# Adorkable_Base_V2.net
KiCad netlist of a schematic drawn in EasyEDA Pro
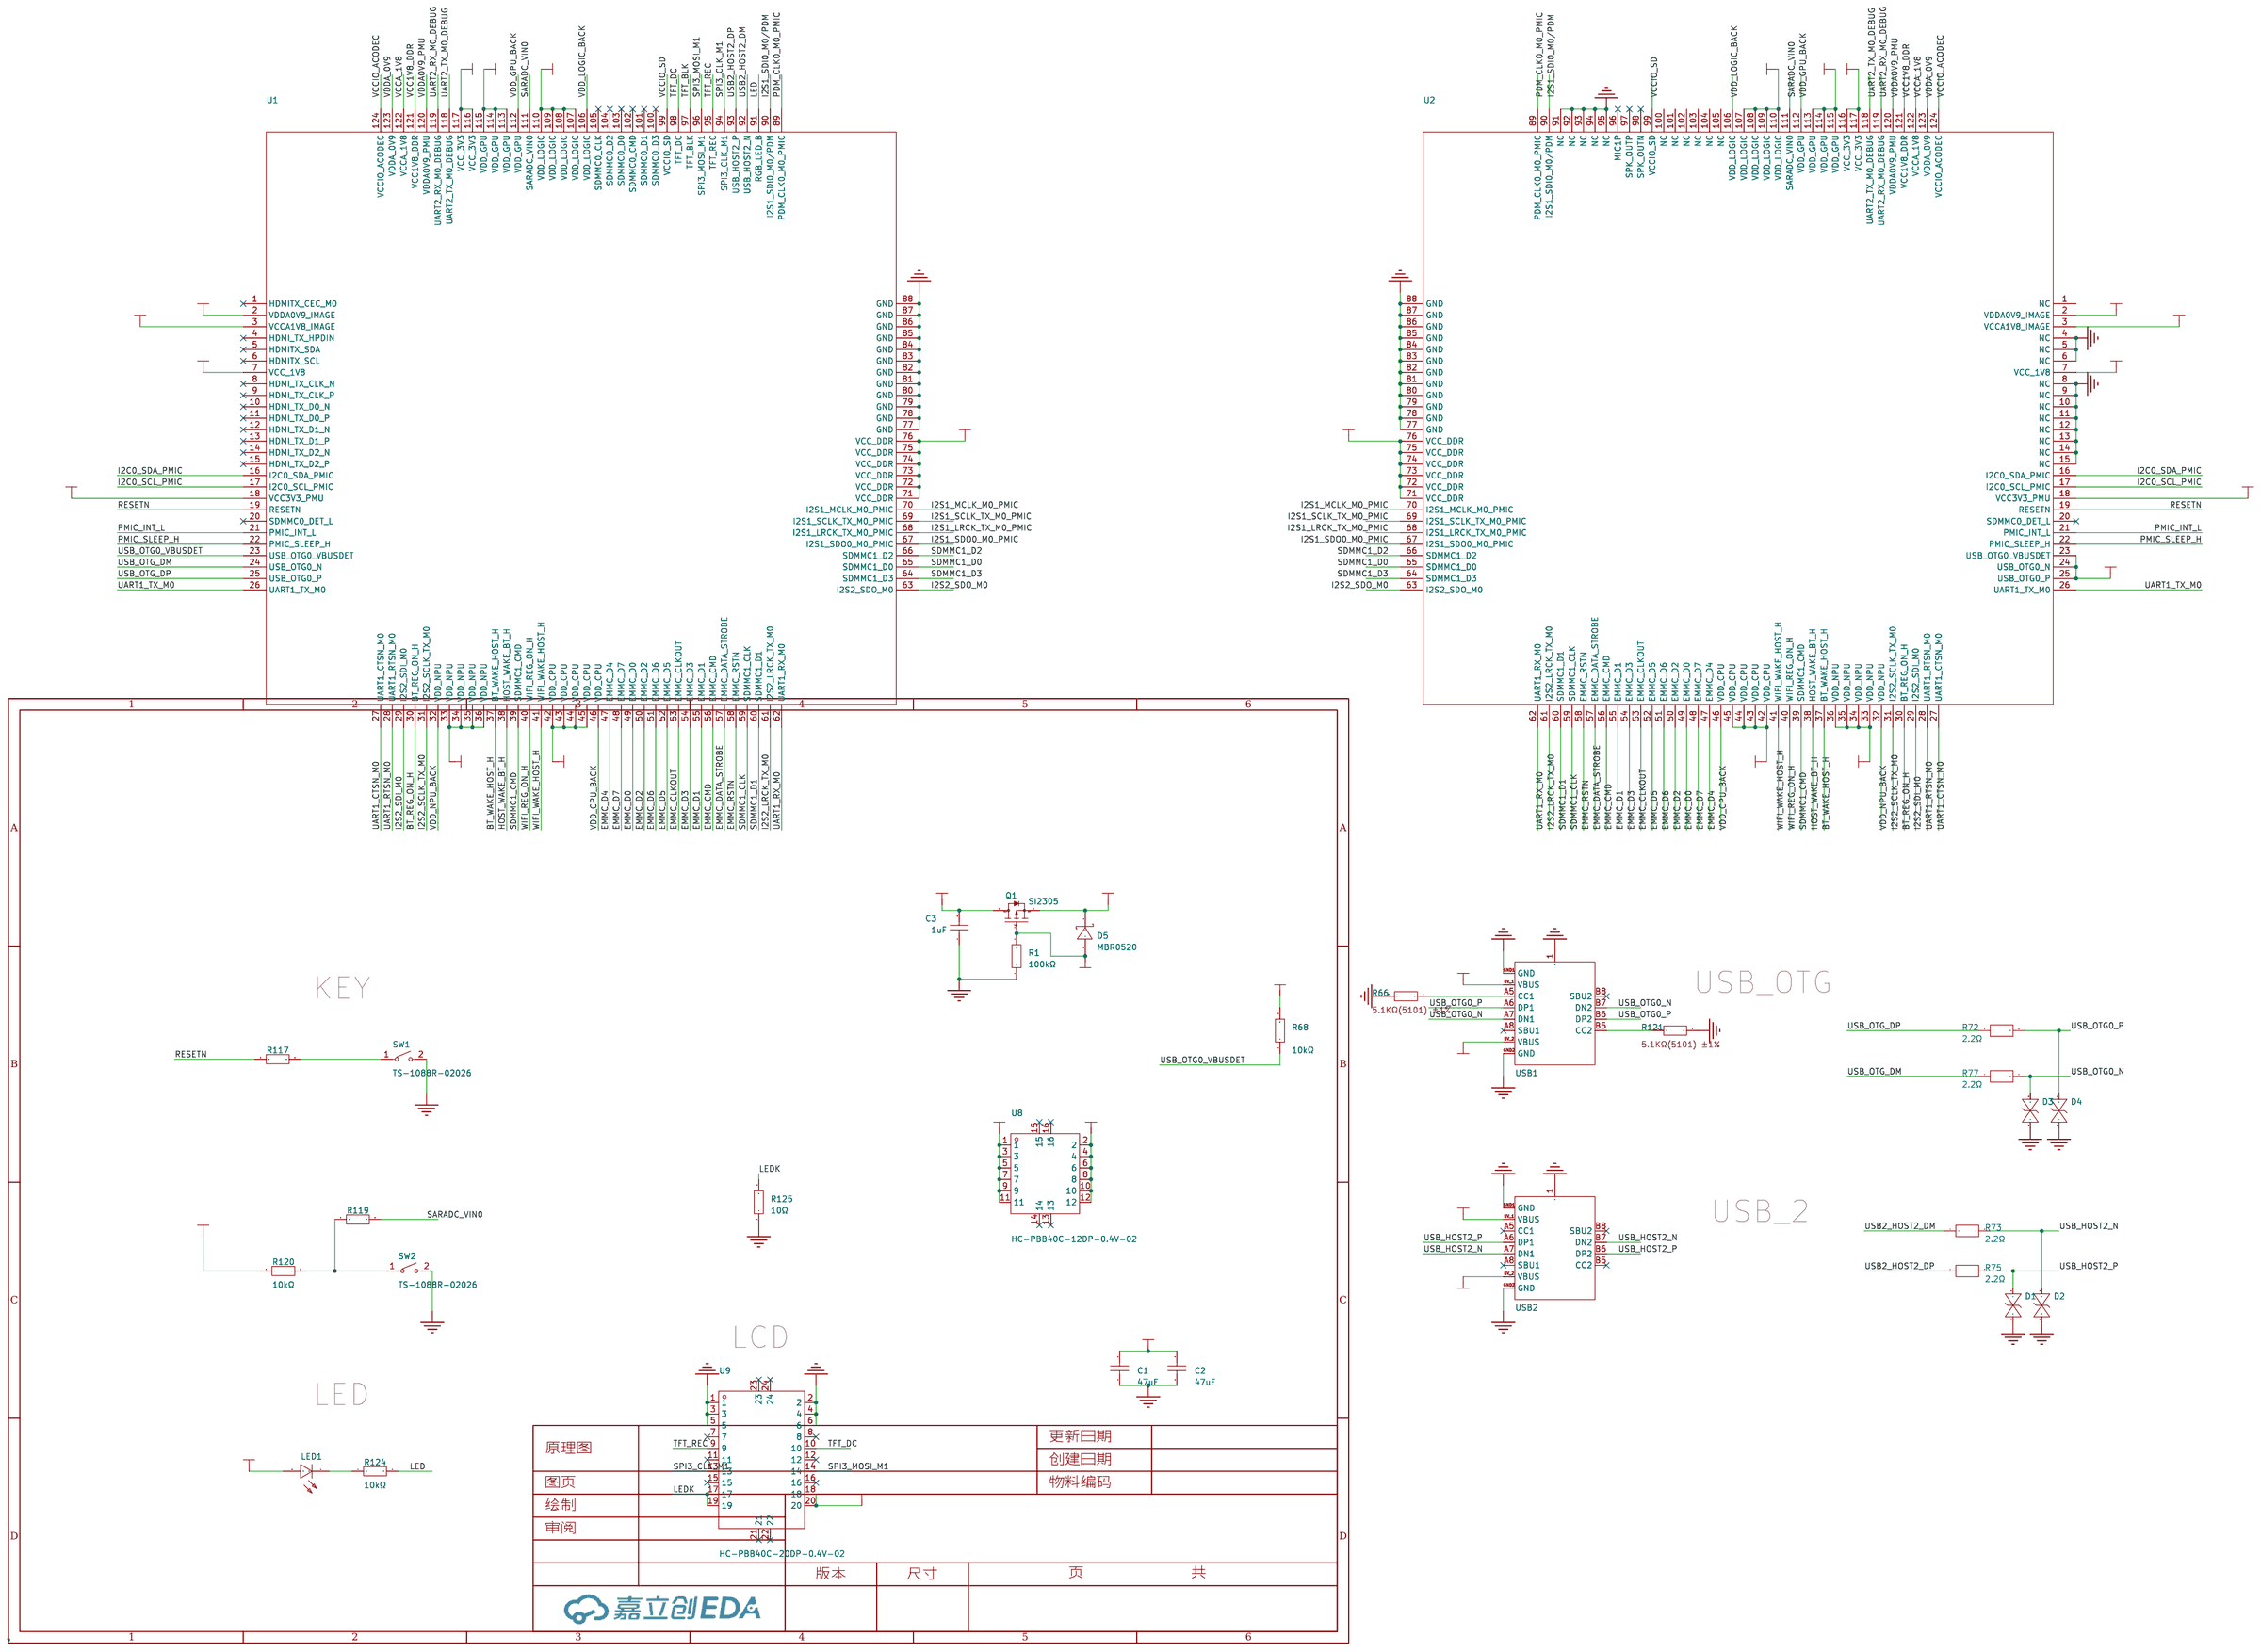
[diagram p0: schematic sheet]

(export (version "E")
  (design (tool "Eeschema 10.0.6"))
  (components
    (comp (ref "C1")
      (value "47uF")
      (footprint "easyedapro:C0603")
      (description "容值:47uF;精度:±20%;额定电压:6.3V;材质(温度系数):X5R;")
      (fields
        (field (name "Manufacturer Part") "GRM188R60J476ME15D")
        (field (name "Manufacturer") "muRata(村田)")
      )
      (libsource (lib "easyedapro") (part "GRM188R60J476ME15D"))
    )
    (comp (ref "C2")
      (value "47uF")
      (footprint "easyedapro:C0603")
      (description "容值:47uF;精度:±20%;额定电压:6.3V;材质(温度系数):X5R;")
      (fields
        (field (name "Manufacturer Part") "GRM188R60J476ME15D")
        (field (name "Manufacturer") "muRata(村田)")
      )
      (libsource (lib "easyedapro") (part "GRM188R60J476ME15D"))
    )
    (comp (ref "C3")
      (value "1uF")
      (footprint "easyedapro:C0402")
      (description "容值:1uF;精度:±10%;额定电压:10V;材质(温度系数):X5R;")
      (fields
        (field (name "Manufacturer Part") "CL05A105KP5NNNC")
        (field (name "Manufacturer") "SAMSUNG(三星)")
      )
      (libsource (lib "easyedapro") (part "CL05A105KP5NNNC"))
    )
    (comp (ref "D1")
      (value "KLXES15AAA1")
      (footprint "easyedapro:D0402-BI")
      (description "极性:双向;反向截止电压(Vrwm):5V;钳位电压(Vc)@Ipp:40V;")
      (fields (field (name "Manufacturer") "KUU"))
      (libsource (lib "easyedapro") (part "KLXES15AAA1"))
    )
    (comp (ref "D2")
      (value "KLXES15AAA1")
      (footprint "easyedapro:D0402-BI")
      (description "极性:双向;反向截止电压(Vrwm):5V;钳位电压(Vc)@Ipp:40V;")
      (fields (field (name "Manufacturer") "KUU"))
      (libsource (lib "easyedapro") (part "KLXES15AAA1"))
    )
    (comp (ref "D3")
      (value "KLXES15AAA1")
      (footprint "easyedapro:D0402-BI")
      (description "极性:双向;反向截止电压(Vrwm):5V;钳位电压(Vc)@Ipp:40V;")
      (fields (field (name "Manufacturer") "KUU"))
      (libsource (lib "easyedapro") (part "KLXES15AAA1"))
    )
    (comp (ref "D4")
      (value "KLXES15AAA1")
      (footprint "easyedapro:D0402-BI")
      (description "极性:双向;反向截止电压(Vrwm):5V;钳位电压(Vc)@Ipp:40V;")
      (fields (field (name "Manufacturer") "KUU"))
      (libsource (lib "easyedapro") (part "KLXES15AAA1"))
    )
    (comp (ref "D5")
      (value "MBR0520")
      (footprint "easyedapro:SOD-123_L2.8-W1.8-LS3.7-RD")
      (description "正向压降(Vf):450mV@500mA;直流反向耐压(Vr):20V;平均整流电流(Io):500mA;")
      (fields (field (name "Manufacturer") "CJ(江苏长电/长晶)"))
      (libsource (lib "easyedapro") (part "MBR0520"))
    )
    (comp (ref "LED1")
      (value "19-217/GHC-YR1S2/3T")
      (footprint "easyedapro:LED0603-RD")
      (description "发光颜色:翠绿;二极管配置:-;主波长:520nm~535nm;色温:-;功率:110mW;安装方式:-;")
      (fields (field (name "Manufacturer") "EVERLIGHT(亿光)"))
      (libsource (lib "easyedapro") (part "19-217/GHC-YR1S2/3T"))
    )
    (comp (ref "Q1")
      (value "SI2305")
      (footprint "easyedapro:SOT-23-3_L2.9-W1.3-P1.90-LS2.4-BR")
      (fields (field (name "Manufacturer") "Hottech(合科泰)"))
      (libsource (lib "easyedapro") (part "SI2305"))
    )
    (comp (ref "R1")
      (value "100kΩ")
      (footprint "easyedapro:R0402")
      (description "电阻类型:厚膜电阻;阻值:100kΩ;精度:±1%;功率:62.5mW;最大工作电压:50V;温度系数:±100ppm/°C;")
      (fields
        (field (name "Manufacturer Part") "0402WGF1003TCE")
        (field (name "Manufacturer") "UNI-ROYAL(厚声)")
      )
      (libsource (lib "easyedapro") (part "0402WGF1003TCE"))
    )
    (comp (ref "R66")
      (value "0402WGF5101TCE")
      (footprint "easyedapro:R0402")
      (fields (field (name "Manufacturer") "UNI-ROYAL(厚声)") (field (name "LCSC Part Name") "5.1KΩ(5101) ±1%"))
      (libsource (lib "easyedapro") (part "0402WGF5101TCE"))
    )
    (comp (ref "R68")
      (value "10kΩ")
      (footprint "easyedapro:R0402")
      (description "电阻类型:厚膜电阻;阻值:10kΩ;精度:±1%;功率:63mW;温度系数:±100ppm/K;最大工作电压:50V;工作温度范围:-55°C~+155°C;")
      (fields
        (field (name "Manufacturer Part") "CRCW040210K0FKED")
        (field (name "Manufacturer") "VISHAY(威世)")
      )
      (libsource (lib "easyedapro") (part "CRCW040210K0FKED"))
    )
    (comp (ref "R72")
      (value "2.2Ω")
      (footprint "easyedapro:R0402")
      (description "电阻类型:厚膜电阻;阻值:2.2Ω;精度:±5%;功率:100mW;温度系数:-100ppm/°C~+600ppm/°C;最大工作电压:-;工作温度范围:-55°C~+155°C;")
      (fields (field (name "Manufacturer Part") "ERJ2GEJ2R2X") (field (name "Manufacturer") "PANASONIC(松下)"))
      (libsource (lib "easyedapro") (part "ERJ2GEJ2R2X"))
    )
    (comp (ref "R73")
      (value "2.2Ω")
      (footprint "easyedapro:R0402")
      (description "电阻类型:厚膜电阻;阻值:2.2Ω;精度:±5%;功率:100mW;温度系数:-100ppm/°C~+600ppm/°C;最大工作电压:-;工作温度范围:-55°C~+155°C;")
      (fields (field (name "Manufacturer Part") "ERJ2GEJ2R2X") (field (name "Manufacturer") "PANASONIC(松下)"))
      (libsource (lib "easyedapro") (part "ERJ2GEJ2R2X"))
    )
    (comp (ref "R75")
      (value "2.2Ω")
      (footprint "easyedapro:R0402")
      (description "电阻类型:厚膜电阻;阻值:2.2Ω;精度:±5%;功率:100mW;温度系数:-100ppm/°C~+600ppm/°C;最大工作电压:-;工作温度范围:-55°C~+155°C;")
      (fields (field (name "Manufacturer Part") "ERJ2GEJ2R2X") (field (name "Manufacturer") "PANASONIC(松下)"))
      (libsource (lib "easyedapro") (part "ERJ2GEJ2R2X"))
    )
    (comp (ref "R77")
      (value "2.2Ω")
      (footprint "easyedapro:R0402")
      (description "电阻类型:厚膜电阻;阻值:2.2Ω;精度:±5%;功率:100mW;温度系数:-100ppm/°C~+600ppm/°C;最大工作电压:-;工作温度范围:-55°C~+155°C;")
      (fields (field (name "Manufacturer Part") "ERJ2GEJ2R2X") (field (name "Manufacturer") "PANASONIC(松下)"))
      (libsource (lib "easyedapro") (part "ERJ2GEJ2R2X"))
    )
    (comp (ref "R117")
      (value "0402WGF1000TCE")
      (footprint "easyedapro:R0402")
      (fields (field (name "Manufacturer") "UNI-ROYAL(厚声)"))
      (libsource (lib "easyedapro") (part "0402WGF1000TCE"))
    )
    (comp (ref "R119")
      (value "0402WGF1000TCE")
      (footprint "easyedapro:R0402")
      (fields (field (name "Manufacturer") "UNI-ROYAL(厚声)"))
      (libsource (lib "easyedapro") (part "0402WGF1000TCE"))
    )
    (comp (ref "R120")
      (value "10kΩ")
      (footprint "easyedapro:R0402")
      (description "电阻类型:厚膜电阻;阻值:10kΩ;精度:±1%;功率:62.5mW;")
      (fields
        (field (name "Manufacturer Part") "0402WGF1002TCE")
        (field (name "Manufacturer") "UNI-ROYAL(厚声)")
      )
      (libsource (lib "easyedapro") (part "0402WGF1002TCE"))
    )
    (comp (ref "R121")
      (value "0402WGF5101TCE")
      (footprint "easyedapro:R0402")
      (fields (field (name "Manufacturer") "UNI-ROYAL(厚声)") (field (name "LCSC Part Name") "5.1KΩ(5101) ±1%"))
      (libsource (lib "easyedapro") (part "0402WGF5101TCE"))
    )
    (comp (ref "R124")
      (value "10kΩ")
      (footprint "easyedapro:R0402")
      (description "电阻类型:厚膜电阻;阻值:10kΩ;精度:±1%;功率:62.5mW;")
      (fields
        (field (name "Manufacturer Part") "0402WGF1002TCE")
        (field (name "Manufacturer") "UNI-ROYAL(厚声)")
      )
      (libsource (lib "easyedapro") (part "0402WGF1002TCE"))
    )
    (comp (ref "R125")
      (value "10Ω")
      (footprint "easyedapro:R0402")
      (description "电阻类型:厚膜电阻;阻值:10Ω;精度:±1%;功率:62.5mW;最大工作电压:50V;温度系数:±200ppm/°C;")
      (fields
        (field (name "Manufacturer Part") "0402WGF100JTCE")
        (field (name "Manufacturer") "UNI-ROYAL(厚声)")
      )
      (libsource (lib "easyedapro") (part "0402WGF100JTCE"))
    )
    (comp (ref "SW1")
      (value "TS-1088R-02026")
      (footprint "easyedapro:SW-SMD_L3.9-W3.0-P4.45")
      (description "电路结构:单刀单掷;按钮形状:圆形按钮;安装方式:立贴;开关长度:3.9mm;开关宽度:2.93mm;开关高度:2mm;触点电流:50mA;额定电压(DC):12V;带灯:-;机械寿命:-;")
      (fields (field (name "Manufacturer") "XUNPU(讯普)"))
      (libsource (lib "easyedapro") (part "TS-1088R-02026"))
    )
    (comp (ref "SW2")
      (value "TS-1088R-02026")
      (footprint "easyedapro:SW-SMD_L3.9-W3.0-P4.45")
      (description "电路结构:单刀单掷;按钮形状:圆形按钮;安装方式:立贴;开关长度:3.9mm;开关宽度:2.93mm;开关高度:2mm;触点电流:50mA;额定电压(DC):12V;带灯:-;机械寿命:-;")
      (fields (field (name "Manufacturer") "XUNPU(讯普)"))
      (libsource (lib "easyedapro") (part "TS-1088R-02026"))
    )
    (comp (ref "U1") (value "~") (footprint "easyedapro:Core") (libsource (lib "easyedapro") (part "Core")))
    (comp (ref "U2") (value "~") (footprint "easyedapro:EXP") (libsource (lib "easyedapro") (part "EXP")))
    (comp (ref "U8")
      (value "HC-PBB40C-12DP-0.4V-02")
      (footprint "easyedapro:CONN-SMD_12P-P0.40_HCTL_HC-PBB40C-12DP-0.4V-02")
      (description "PIN总数:12P;间距:0.4mm;安装方式:立贴;排数:2;额定电流:300mA;工作温度:-35°C~+85°C;")
      (fields (field (name "Manufacturer") "HCTL(华灿天禄)"))
      (libsource (lib "easyedapro") (part "HC-PBB40C-12DP-0.4V-02"))
    )
    (comp (ref "U9")
      (value "HC-PBB40C-20DP-0.4V-02")
      (footprint "easyedapro:CONN-SMD_20P-P0.40_HCTL_HC-PBB40C-20DP-0.4V-02")
      (description "PIN总数:20P;间距:0.4mm;安装方式:立贴;排数:2;额定电流:300mA;工作温度:-35°C~+85°C;")
      (fields (field (name "Manufacturer") "HCTL(华灿天禄)"))
      (libsource (lib "easyedapro") (part "HC-PBB40C-20DP-0.4V-02"))
    )
    (comp (ref "USB1")
      (value "~")
      (footprint "easyedapro:TYPE-C-SMD_TYPE-CF3.1")
      (libsource (lib "easyedapro") (part "TYPE-C-16PIN"))
    )
    (comp (ref "USB2")
      (value "~")
      (footprint "easyedapro:TYPE-C-SMD_TYPE-CF3.1")
      (libsource (lib "easyedapro") (part "TYPE-C-16PIN"))
    )
  )
  (nets
    (net (code "1") (name "/BT_REG_ON_H") (class "Default")
      (node (ref "U1") (pin "30") (pinfunction "BT_REG_ON_H_30") (pintype "input"))
      (node (ref "U2") (pin "30") (pinfunction "BT_REG_ON_H_30") (pintype "input"))
    )
    (net (code "2") (name "/BT_WAKE_HOST_H") (class "Default")
      (node (ref "U1") (pin "37") (pinfunction "BT_WAKE_HOST_H_37") (pintype "input"))
      (node (ref "U2") (pin "37") (pinfunction "BT_WAKE_HOST_H_37") (pintype "input"))
    )
    (net (code "3") (name "/EMMC_CLKOUT") (class "Default")
      (node (ref "U1") (pin "53") (pinfunction "EMMC_CLKOUT_53") (pintype "input"))
      (node (ref "U2") (pin "53") (pinfunction "EMMC_CLKOUT_53") (pintype "input"))
    )
    (net (code "4") (name "/EMMC_CMD") (class "Default")
      (node (ref "U1") (pin "56") (pinfunction "EMMC_CMD_56") (pintype "input"))
      (node (ref "U2") (pin "56") (pinfunction "EMMC_CMD_56") (pintype "input"))
    )
    (net (code "5") (name "/EMMC_D0") (class "Default")
      (node (ref "U1") (pin "49") (pinfunction "EMMC_D0_49") (pintype "input"))
      (node (ref "U2") (pin "49") (pinfunction "EMMC_D0_49") (pintype "input"))
    )
    (net (code "6") (name "/EMMC_D1") (class "Default")
      (node (ref "U1") (pin "55") (pinfunction "EMMC_D1_55") (pintype "input"))
      (node (ref "U2") (pin "55") (pinfunction "EMMC_D1_55") (pintype "input"))
    )
    (net (code "7") (name "/EMMC_D2") (class "Default")
      (node (ref "U1") (pin "50") (pinfunction "EMMC_D2_50") (pintype "input"))
      (node (ref "U2") (pin "50") (pinfunction "EMMC_D2_50") (pintype "input"))
    )
    (net (code "8") (name "/EMMC_D3") (class "Default")
      (node (ref "U1") (pin "54") (pinfunction "EMMC_D3_54") (pintype "input"))
      (node (ref "U2") (pin "54") (pinfunction "EMMC_D3_54") (pintype "input"))
    )
    (net (code "9") (name "/EMMC_D4") (class "Default")
      (node (ref "U1") (pin "47") (pinfunction "EMMC_D4_47") (pintype "input"))
      (node (ref "U2") (pin "47") (pinfunction "EMMC_D4_47") (pintype "input"))
    )
    (net (code "10") (name "/EMMC_D5") (class "Default")
      (node (ref "U1") (pin "52") (pinfunction "EMMC_D5_52") (pintype "input"))
      (node (ref "U2") (pin "52") (pinfunction "EMMC_D5_52") (pintype "input"))
    )
    (net (code "11") (name "/EMMC_D6") (class "Default")
      (node (ref "U1") (pin "51") (pinfunction "EMMC_D6_51") (pintype "input"))
      (node (ref "U2") (pin "51") (pinfunction "EMMC_D6_51") (pintype "input"))
    )
    (net (code "12") (name "/EMMC_D7") (class "Default")
      (node (ref "U1") (pin "48") (pinfunction "EMMC_D7_48") (pintype "input"))
      (node (ref "U2") (pin "48") (pinfunction "EMMC_D7_48") (pintype "input"))
    )
    (net (code "13") (name "/EMMC_DATA_STROBE") (class "Default")
      (node (ref "U1") (pin "57") (pinfunction "EMMC_DATA_STROBE_57") (pintype "input"))
      (node (ref "U2") (pin "57") (pinfunction "EMMC_DATA_STROBE_57") (pintype "input"))
    )
    (net (code "14") (name "/EMMC_RSTN") (class "Default")
      (node (ref "U1") (pin "58") (pinfunction "EMMC_RSTN_58") (pintype "input"))
      (node (ref "U2") (pin "58") (pinfunction "EMMC_RSTN_58") (pintype "input"))
    )
    (net (code "15") (name "/HOST_WAKE_BT_H") (class "Default")
      (node (ref "U1") (pin "38") (pinfunction "HOST_WAKE_BT_H_38") (pintype "input"))
      (node (ref "U2") (pin "38") (pinfunction "HOST_WAKE_BT_H_38") (pintype "input"))
    )
    (net (code "16") (name "/I2C0_SCL_PMIC") (class "Default")
      (node (ref "U1") (pin "17") (pinfunction "I2C0_SCL_PMIC_17") (pintype "input"))
      (node (ref "U2") (pin "17") (pinfunction "I2C0_SCL_PMIC_17") (pintype "input"))
    )
    (net (code "17") (name "/I2C0_SDA_PMIC") (class "Default")
      (node (ref "U1") (pin "16") (pinfunction "I2C0_SDA_PMIC_16") (pintype "input"))
      (node (ref "U2") (pin "16") (pinfunction "I2C0_SDA_PMIC_16") (pintype "input"))
    )
    (net (code "18") (name "/I2S1_LRCK_TX_M0_PMIC") (class "Default")
      (node (ref "U1") (pin "68") (pinfunction "I2S1_LRCK_TX_M0_PMIC_68") (pintype "input"))
      (node (ref "U2") (pin "68") (pinfunction "I2S1_LRCK_TX_M0_PMIC_68") (pintype "input"))
    )
    (net (code "19") (name "/I2S1_MCLK_M0_PMIC") (class "Default")
      (node (ref "U1") (pin "70") (pinfunction "I2S1_MCLK_M0_PMIC_70") (pintype "input"))
      (node (ref "U2") (pin "70") (pinfunction "I2S1_MCLK_M0_PMIC_70") (pintype "input"))
    )
    (net (code "20") (name "/I2S1_SCLK_TX_M0_PMIC") (class "Default")
      (node (ref "U1") (pin "69") (pinfunction "I2S1_SCLK_TX_M0_PMIC_69") (pintype "input"))
      (node (ref "U2") (pin "69") (pinfunction "I2S1_SCLK_TX_M0_PMIC_69") (pintype "input"))
    )
    (net (code "21") (name "/I2S1_SDI0_M0{slash}PDM") (class "Default")
      (node (ref "U1") (pin "90") (pinfunction "I2S1_SDI0_M0/PDM_90") (pintype "input"))
      (node (ref "U2") (pin "90") (pinfunction "I2S1_SDI0_M0/PDM_90") (pintype "input"))
    )
    (net (code "22") (name "/I2S1_SDO0_M0_PMIC") (class "Default")
      (node (ref "U1") (pin "67") (pinfunction "I2S1_SDO0_M0_PMIC_67") (pintype "input"))
      (node (ref "U2") (pin "67") (pinfunction "I2S1_SDO0_M0_PMIC_67") (pintype "input"))
    )
    (net (code "23") (name "/I2S2_LRCK_TX_M0") (class "Default")
      (node (ref "U1") (pin "61") (pinfunction "I2S2_LRCK_TX_M0_61") (pintype "input"))
      (node (ref "U2") (pin "61") (pinfunction "I2S2_LRCK_TX_M0_61") (pintype "input"))
    )
    (net (code "24") (name "/I2S2_SCLK_TX_M0") (class "Default")
      (node (ref "U1") (pin "31") (pinfunction "I2S2_SCLK_TX_M0_31") (pintype "input"))
      (node (ref "U2") (pin "31") (pinfunction "I2S2_SCLK_TX_M0_31") (pintype "input"))
    )
    (net (code "25") (name "/I2S2_SDI_M0") (class "Default")
      (node (ref "U1") (pin "29") (pinfunction "I2S2_SDI_M0_29") (pintype "input"))
      (node (ref "U2") (pin "29") (pinfunction "I2S2_SDI_M0_29") (pintype "input"))
    )
    (net (code "26") (name "/I2S2_SDO_M0") (class "Default")
      (node (ref "U1") (pin "63") (pinfunction "I2S2_SDO_M0_63") (pintype "input"))
      (node (ref "U2") (pin "63") (pinfunction "I2S2_SDO_M0_63") (pintype "input"))
    )
    (net (code "27") (name "/LED") (class "Default")
      (node (ref "R124") (pin "2") (pinfunction "2_2") (pintype "input"))
      (node (ref "U1") (pin "91") (pinfunction "RGB_LED_B_91") (pintype "input"))
    )
    (net (code "28") (name "/LEDK") (class "Default")
      (node (ref "R125") (pin "2") (pinfunction "2_2") (pintype "input"))
      (node (ref "U9") (pin "17") (pinfunction "17_17") (pintype "unspecified"))
      (node (ref "U9") (pin "19") (pinfunction "19_19") (pintype "unspecified"))
    )
    (net (code "29") (name "/PDM_CLK0_M0_PMIC") (class "Default")
      (node (ref "U1") (pin "89") (pinfunction "PDM_CLK0_M0_PMIC_89") (pintype "input"))
      (node (ref "U2") (pin "89") (pinfunction "PDM_CLK0_M0_PMIC_89") (pintype "input"))
    )
    (net (code "30") (name "/PMIC_INT_L") (class "Default")
      (node (ref "U1") (pin "21") (pinfunction "PMIC_INT_L_21") (pintype "input"))
      (node (ref "U2") (pin "21") (pinfunction "PMIC_INT_L_21") (pintype "input"))
    )
    (net (code "31") (name "/PMIC_SLEEP_H") (class "Default")
      (node (ref "U1") (pin "22") (pinfunction "PMIC_SLEEP_H_22") (pintype "input"))
      (node (ref "U2") (pin "22") (pinfunction "PMIC_SLEEP_H_22") (pintype "input"))
    )
    (net (code "32") (name "/RESETN") (class "Default")
      (node (ref "R117") (pin "1") (pinfunction "1_1") (pintype "input"))
      (node (ref "U1") (pin "19") (pinfunction "RESETN_19") (pintype "input"))
      (node (ref "U2") (pin "19") (pinfunction "RESETN_19") (pintype "input"))
    )
    (net (code "33") (name "/SARADC_VIN0") (class "Default")
      (node (ref "R119") (pin "2") (pinfunction "2_2") (pintype "input"))
      (node (ref "U1") (pin "111") (pinfunction "SARADC_VIN0_111") (pintype "input"))
      (node (ref "U2") (pin "111") (pinfunction "SARADC_VIN0_111") (pintype "input"))
    )
    (net (code "34") (name "/SDMMC1_CLK") (class "Default")
      (node (ref "U1") (pin "59") (pinfunction "SDMMC1_CLK_59") (pintype "input"))
      (node (ref "U2") (pin "59") (pinfunction "SDMMC1_CLK_59") (pintype "input"))
    )
    (net (code "35") (name "/SDMMC1_CMD") (class "Default")
      (node (ref "U1") (pin "39") (pinfunction "SDMMC1_CMD_39") (pintype "input"))
      (node (ref "U2") (pin "39") (pinfunction "SDMMC1_CMD_39") (pintype "input"))
    )
    (net (code "36") (name "/SDMMC1_D0") (class "Default")
      (node (ref "U1") (pin "65") (pinfunction "SDMMC1_D0_65") (pintype "input"))
      (node (ref "U2") (pin "65") (pinfunction "SDMMC1_D0_65") (pintype "input"))
    )
    (net (code "37") (name "/SDMMC1_D1") (class "Default")
      (node (ref "U1") (pin "60") (pinfunction "SDMMC1_D1_60") (pintype "input"))
      (node (ref "U2") (pin "60") (pinfunction "SDMMC1_D1_60") (pintype "input"))
    )
    (net (code "38") (name "/SDMMC1_D2") (class "Default")
      (node (ref "U1") (pin "66") (pinfunction "SDMMC1_D2_66") (pintype "input"))
      (node (ref "U2") (pin "66") (pinfunction "SDMMC1_D2_66") (pintype "input"))
    )
    (net (code "39") (name "/SDMMC1_D3") (class "Default")
      (node (ref "U1") (pin "64") (pinfunction "SDMMC1_D3_64") (pintype "input"))
      (node (ref "U2") (pin "64") (pinfunction "SDMMC1_D3_64") (pintype "input"))
    )
    (net (code "40") (name "/SPI3_CLK_M1") (class "Default")
      (node (ref "U1") (pin "94") (pinfunction "SPI3_CLK_M1_94") (pintype "input"))
      (node (ref "U9") (pin "13") (pinfunction "13_13") (pintype "unspecified"))
    )
    (net (code "41") (name "/SPI3_MOSI_M1") (class "Default")
      (node (ref "U1") (pin "96") (pinfunction "SPI3_MOSI_M1_96") (pintype "input"))
      (node (ref "U9") (pin "14") (pinfunction "14_14") (pintype "unspecified"))
    )
    (net (code "42") (name "/TFT_BLK") (class "Default")
      (node (ref "U1") (pin "97") (pinfunction "TFT_BLK_97") (pintype "input"))
    )
    (net (code "43") (name "/TFT_DC") (class "Default")
      (node (ref "U1") (pin "98") (pinfunction "TFT_DC_98") (pintype "input"))
      (node (ref "U9") (pin "10") (pinfunction "10_10") (pintype "unspecified"))
    )
    (net (code "44") (name "/TFT_REC") (class "Default")
      (node (ref "U1") (pin "95") (pinfunction "TFT_REC_95") (pintype "input"))
      (node (ref "U9") (pin "9") (pinfunction "9_9") (pintype "unspecified"))
    )
    (net (code "45") (name "/UART1_CTSN_M0") (class "Default")
      (node (ref "U1") (pin "27") (pinfunction "UART1_CTSN_M0_27") (pintype "input"))
      (node (ref "U2") (pin "27") (pinfunction "UART1_CTSN_M0_27") (pintype "input"))
    )
    (net (code "46") (name "/UART1_RTSN_M0") (class "Default")
      (node (ref "U1") (pin "28") (pinfunction "UART1_RTSN_M0_28") (pintype "input"))
      (node (ref "U2") (pin "28") (pinfunction "UART1_RTSN_M0_28") (pintype "input"))
    )
    (net (code "47") (name "/UART1_RX_M0") (class "Default")
      (node (ref "U1") (pin "62") (pinfunction "UART1_RX_M0_62") (pintype "input"))
      (node (ref "U2") (pin "62") (pinfunction "UART1_RX_M0_62") (pintype "input"))
    )
    (net (code "48") (name "/UART1_TX_M0") (class "Default")
      (node (ref "U1") (pin "26") (pinfunction "UART1_TX_M0_26") (pintype "input"))
      (node (ref "U2") (pin "26") (pinfunction "UART1_TX_M0_26") (pintype "input"))
    )
    (net (code "49") (name "/UART2_RX_M0_DEBUG") (class "Default")
      (node (ref "U1") (pin "119") (pinfunction "UART2_RX_M0_DEBUG_119") (pintype "input"))
      (node (ref "U2") (pin "119") (pinfunction "UART2_RX_M0_DEBUG_119") (pintype "input"))
    )
    (net (code "50") (name "/UART2_TX_M0_DEBUG") (class "Default")
      (node (ref "U1") (pin "118") (pinfunction "UART2_TX_M0_DEBUG_118") (pintype "input"))
      (node (ref "U2") (pin "118") (pinfunction "UART2_TX_M0_DEBUG_118") (pintype "input"))
    )
    (net (code "51") (name "/USB2_HOST2_DM") (class "Default")
      (node (ref "R73") (pin "1") (pinfunction "1_1") (pintype "input"))
      (node (ref "U1") (pin "92") (pinfunction "USB_HOST2_N_92") (pintype "input"))
    )
    (net (code "52") (name "/USB2_HOST2_DP") (class "Default")
      (node (ref "R75") (pin "1") (pinfunction "1_1") (pintype "input"))
      (node (ref "U1") (pin "93") (pinfunction "USB_HOST2_P_93") (pintype "input"))
    )
    (net (code "53") (name "/USB_HOST2_N") (class "Default")
      (node (ref "D2") (pin "2") (pinfunction "A_2") (pintype "input"))
      (node (ref "R73") (pin "2") (pinfunction "2_2") (pintype "input"))
      (node (ref "USB2") (pin "A7") (pinfunction "DN1_A7") (pintype "unspecified"))
      (node (ref "USB2") (pin "B7") (pinfunction "DN2_B7") (pintype "unspecified"))
    )
    (net (code "54") (name "/USB_HOST2_P") (class "Default")
      (node (ref "D1") (pin "2") (pinfunction "A_2") (pintype "input"))
      (node (ref "R75") (pin "2") (pinfunction "2_2") (pintype "input"))
      (node (ref "USB2") (pin "A6") (pinfunction "DP1_A6") (pintype "unspecified"))
      (node (ref "USB2") (pin "B6") (pinfunction "DP2_B6") (pintype "unspecified"))
    )
    (net (code "55") (name "/USB_OTG0_N") (class "Default")
      (node (ref "D3") (pin "2") (pinfunction "A_2") (pintype "input"))
      (node (ref "R77") (pin "2") (pinfunction "2_2") (pintype "input"))
      (node (ref "USB1") (pin "A7") (pinfunction "DN1_A7") (pintype "unspecified"))
      (node (ref "USB1") (pin "B7") (pinfunction "DN2_B7") (pintype "unspecified"))
    )
    (net (code "56") (name "/USB_OTG0_P") (class "Default")
      (node (ref "D4") (pin "2") (pinfunction "A_2") (pintype "input"))
      (node (ref "R72") (pin "2") (pinfunction "2_2") (pintype "input"))
      (node (ref "USB1") (pin "A6") (pinfunction "DP1_A6") (pintype "unspecified"))
      (node (ref "USB1") (pin "B6") (pinfunction "DP2_B6") (pintype "unspecified"))
    )
    (net (code "57") (name "/USB_OTG0_VBUSDET") (class "Default")
      (node (ref "R68") (pin "1") (pinfunction "1_1") (pintype "input"))
      (node (ref "U1") (pin "23") (pinfunction "USB_OTG0_VBUSDET_23") (pintype "input"))
    )
    (net (code "58") (name "/USB_OTG_DM") (class "Default")
      (node (ref "R77") (pin "1") (pinfunction "1_1") (pintype "input"))
      (node (ref "U1") (pin "24") (pinfunction "USB_OTG0_N_24") (pintype "input"))
    )
    (net (code "59") (name "/USB_OTG_DP") (class "Default")
      (node (ref "R72") (pin "1") (pinfunction "1_1") (pintype "input"))
      (node (ref "U1") (pin "25") (pinfunction "USB_OTG0_P_25") (pintype "input"))
    )
    (net (code "60") (name "/VCC1V8_DDR") (class "Default")
      (node (ref "U1") (pin "121") (pinfunction "VCC1V8_DDR_121") (pintype "input"))
      (node (ref "U2") (pin "121") (pinfunction "VCC1V8_DDR_121") (pintype "input"))
    )
    (net (code "61") (name "/VCCIO_ACODEC") (class "Default")
      (node (ref "U1") (pin "124") (pinfunction "VCCIO_ACODEC_124") (pintype "input"))
      (node (ref "U2") (pin "124") (pinfunction "VCCIO_ACODEC_124") (pintype "input"))
    )
    (net (code "62") (name "/VCCIO_SD") (class "Default")
      (node (ref "U1") (pin "99") (pinfunction "VCCIO_SD_99") (pintype "input"))
      (node (ref "U2") (pin "99") (pinfunction "VCCIO_SD_99") (pintype "input"))
    )
    (net (code "63") (name "/VDDA0V9_PMU") (class "Default")
      (node (ref "U1") (pin "120") (pinfunction "VDDA0V9_PMU_120") (pintype "input"))
      (node (ref "U2") (pin "120") (pinfunction "VDDA0V9_PMU_120") (pintype "input"))
    )
    (net (code "64") (name "/VDDA_0V9") (class "Default")
      (node (ref "U1") (pin "123") (pinfunction "VDDA_0V9_123") (pintype "input"))
      (node (ref "U2") (pin "123") (pinfunction "VDDA_0V9_123") (pintype "input"))
    )
    (net (code "65") (name "/VDD_CPU_BACK") (class "Default")
      (node (ref "U1") (pin "46") (pinfunction "VDD_CPU_46") (pintype "input"))
      (node (ref "U2") (pin "46") (pinfunction "VDD_CPU_46") (pintype "input"))
    )
    (net (code "66") (name "/VDD_GPU_BACK") (class "Default")
      (node (ref "U1") (pin "112") (pinfunction "VDD_GPU_112") (pintype "input"))
      (node (ref "U2") (pin "112") (pinfunction "VDD_GPU_112") (pintype "input"))
    )
    (net (code "67") (name "/VDD_LOGIC_BACK") (class "Default")
      (node (ref "U1") (pin "106") (pinfunction "VDD_LOGIC_106") (pintype "input"))
      (node (ref "U2") (pin "106") (pinfunction "VDD_LOGIC_106") (pintype "input"))
    )
    (net (code "68") (name "/VDD_NPU_BACK") (class "Default")
      (node (ref "U1") (pin "32") (pinfunction "VDD_NPU_32") (pintype "input"))
      (node (ref "U2") (pin "32") (pinfunction "VDD_NPU_32") (pintype "input"))
    )
    (net (code "69") (name "/WIFI_REG_ON_H") (class "Default")
      (node (ref "U1") (pin "40") (pinfunction "WIFI_REG_ON_H_40") (pintype "input"))
      (node (ref "U2") (pin "40") (pinfunction "WIFI_REG_ON_H_40") (pintype "input"))
    )
    (net (code "70") (name "/WIFI_WAKE_HOST_H") (class "Default")
      (node (ref "U1") (pin "41") (pinfunction "WIFI_WAKE_HOST_H_41") (pintype "input"))
      (node (ref "U2") (pin "41") (pinfunction "WIFI_WAKE_HOST_H_41") (pintype "input"))
    )
    (net (code "71") (name "GND") (class "Default")
      (node (ref "C1") (pin "1") (pinfunction "1_1") (pintype "input"))
      (node (ref "C2") (pin "1") (pinfunction "1_1") (pintype "input"))
      (node (ref "C3") (pin "1") (pinfunction "1_1") (pintype "input"))
      (node (ref "D1") (pin "1") (pinfunction "K_1") (pintype "input"))
      (node (ref "D2") (pin "1") (pinfunction "K_1") (pintype "input"))
      (node (ref "D3") (pin "1") (pinfunction "K_1") (pintype "input"))
      (node (ref "D4") (pin "1") (pinfunction "K_1") (pintype "input"))
      (node (ref "R1") (pin "1") (pinfunction "1_1") (pintype "input"))
      (node (ref "R121") (pin "1") (pinfunction "1_1") (pintype "input"))
      (node (ref "R125") (pin "1") (pinfunction "1_1") (pintype "input"))
      (node (ref "R66") (pin "2") (pinfunction "2_2") (pintype "input"))
      (node (ref "SW1") (pin "2") (pinfunction "2_2") (pintype "unspecified"))
      (node (ref "SW2") (pin "2") (pinfunction "2_2") (pintype "unspecified"))
      (node (ref "U1") (pin "77") (pinfunction "GND_77") (pintype "input"))
      (node (ref "U1") (pin "78") (pinfunction "GND_78") (pintype "input"))
      (node (ref "U1") (pin "79") (pinfunction "GND_79") (pintype "input"))
      (node (ref "U1") (pin "80") (pinfunction "GND_80") (pintype "input"))
      (node (ref "U1") (pin "81") (pinfunction "GND_81") (pintype "input"))
      (node (ref "U1") (pin "82") (pinfunction "GND_82") (pintype "input"))
      (node (ref "U1") (pin "83") (pinfunction "GND_83") (pintype "input"))
      (node (ref "U1") (pin "84") (pinfunction "GND_84") (pintype "input"))
      (node (ref "U1") (pin "85") (pinfunction "GND_85") (pintype "input"))
      (node (ref "U1") (pin "86") (pinfunction "GND_86") (pintype "input"))
      (node (ref "U1") (pin "87") (pinfunction "GND_87") (pintype "input"))
      (node (ref "U1") (pin "88") (pinfunction "GND_88") (pintype "input"))
      (node (ref "U2") (pin "10") (pinfunction "NC_10") (pintype "input"))
      (node (ref "U2") (pin "11") (pinfunction "NC_11") (pintype "input"))
      (node (ref "U2") (pin "12") (pinfunction "NC_12") (pintype "input"))
      (node (ref "U2") (pin "13") (pinfunction "NC_13") (pintype "input"))
      (node (ref "U2") (pin "14") (pinfunction "NC_14") (pintype "input"))
      (node (ref "U2") (pin "15") (pinfunction "NC_15") (pintype "input"))
      (node (ref "U2") (pin "4") (pinfunction "NC_4") (pintype "input"))
      (node (ref "U2") (pin "5") (pinfunction "NC_5") (pintype "input"))
      (node (ref "U2") (pin "6") (pinfunction "NC_6") (pintype "input"))
      (node (ref "U2") (pin "77") (pinfunction "GND_77") (pintype "input"))
      (node (ref "U2") (pin "78") (pinfunction "GND_78") (pintype "input"))
      (node (ref "U2") (pin "79") (pinfunction "GND_79") (pintype "input"))
      (node (ref "U2") (pin "8") (pinfunction "NC_8") (pintype "input"))
      (node (ref "U2") (pin "80") (pinfunction "GND_80") (pintype "input"))
      (node (ref "U2") (pin "81") (pinfunction "GND_81") (pintype "input"))
      (node (ref "U2") (pin "82") (pinfunction "GND_82") (pintype "input"))
      (node (ref "U2") (pin "83") (pinfunction "GND_83") (pintype "input"))
      (node (ref "U2") (pin "84") (pinfunction "GND_84") (pintype "input"))
      (node (ref "U2") (pin "85") (pinfunction "GND_85") (pintype "input"))
      (node (ref "U2") (pin "86") (pinfunction "GND_86") (pintype "input"))
      (node (ref "U2") (pin "87") (pinfunction "GND_87") (pintype "input"))
      (node (ref "U2") (pin "88") (pinfunction "GND_88") (pintype "input"))
      (node (ref "U2") (pin "9") (pinfunction "NC_9") (pintype "input"))
      (node (ref "U2") (pin "91") (pinfunction "NC_91") (pintype "input"))
      (node (ref "U2") (pin "92") (pinfunction "NC_92") (pintype "input"))
      (node (ref "U2") (pin "93") (pinfunction "NC_93") (pintype "input"))
      (node (ref "U2") (pin "94") (pinfunction "NC_94") (pintype "input"))
      (node (ref "U2") (pin "95") (pinfunction "NC_95") (pintype "input"))
      (node (ref "U9") (pin "1") (pinfunction "1_1") (pintype "unspecified"))
      (node (ref "U9") (pin "2") (pinfunction "2_2") (pintype "unspecified"))
      (node (ref "U9") (pin "3") (pinfunction "3_3") (pintype "unspecified"))
      (node (ref "U9") (pin "4") (pinfunction "4_4") (pintype "unspecified"))
      (node (ref "U9") (pin "5") (pinfunction "5_5") (pintype "unspecified"))
      (node (ref "U9") (pin "6") (pinfunction "6_6") (pintype "unspecified"))
      (node (ref "USB1") (pin "1") (pinfunction "EH_1") (pintype "unspecified"))
      (node (ref "USB1") (pin "GND1") (pinfunction "GND_GND1") (pintype "unspecified"))
      (node (ref "USB1") (pin "GND2") (pinfunction "GND_GND2") (pintype "unspecified"))
      (node (ref "USB2") (pin "1") (pinfunction "EH_1") (pintype "unspecified"))
      (node (ref "USB2") (pin "GND1") (pinfunction "GND_GND1") (pintype "unspecified"))
      (node (ref "USB2") (pin "GND2") (pinfunction "GND_GND2") (pintype "unspecified"))
    )
    (net (code "72") (name "Net-(LED1-C)") (class "Default")
      (node (ref "LED1") (pin "1") (pinfunction "C_1") (pintype "input"))
      (node (ref "R124") (pin "1") (pinfunction "1_1") (pintype "input"))
    )
    (net (code "73") (name "Net-(R117-Pad2)") (class "Default")
      (node (ref "R117") (pin "2") (pinfunction "2_2") (pintype "input"))
      (node (ref "SW1") (pin "1") (pinfunction "1_1") (pintype "unspecified"))
    )
    (net (code "74") (name "Net-(R119-Pad1)") (class "Default")
      (node (ref "R119") (pin "1") (pinfunction "1_1") (pintype "input"))
      (node (ref "R120") (pin "2") (pinfunction "2_2") (pintype "input"))
      (node (ref "SW2") (pin "1") (pinfunction "1_1") (pintype "unspecified"))
    )
    (net (code "75") (name "Net-(USB1-CC1)") (class "Default")
      (node (ref "R66") (pin "1") (pinfunction "1_1") (pintype "input"))
      (node (ref "USB1") (pin "A5") (pinfunction "CC1_A5") (pintype "unspecified"))
    )
    (net (code "76") (name "Net-(USB1-CC2)") (class "Default")
      (node (ref "R121") (pin "2") (pinfunction "2_2") (pintype "input"))
      (node (ref "USB1") (pin "B5") (pinfunction "CC2_B5") (pintype "unspecified"))
    )
    (net (code "77") (name "VCC3V3_PMU") (class "Default")
      (node (ref "U1") (pin "18") (pinfunction "VCC3V3_PMU_18") (pintype "input"))
      (node (ref "U2") (pin "18") (pinfunction "VCC3V3_PMU_18") (pintype "input"))
    )
    (net (code "78") (name "VCCA1V8_IMAGE") (class "Default")
      (node (ref "U1") (pin "3") (pinfunction "VCCA1V8_IMAGE_3") (pintype "input"))
      (node (ref "U2") (pin "3") (pinfunction "VCCA1V8_IMAGE_3") (pintype "input"))
    )
    (net (code "79") (name "VCCA_1V8") (class "Default")
      (node (ref "R120") (pin "1") (pinfunction "1_1") (pintype "input"))
      (node (ref "U1") (pin "122") (pinfunction "VCCA_1V8_122") (pintype "input"))
      (node (ref "U2") (pin "122") (pinfunction "VCCA_1V8_122") (pintype "input"))
    )
    (net (code "80") (name "VCC_1V8") (class "Default")
      (node (ref "U1") (pin "7") (pinfunction "VCC_1V8_7") (pintype "input"))
      (node (ref "U2") (pin "7") (pinfunction "VCC_1V8_7") (pintype "input"))
    )
    (net (code "81") (name "VCC_3V3") (class "Default")
      (node (ref "LED1") (pin "2") (pinfunction "A_2") (pintype "input"))
      (node (ref "U1") (pin "116") (pinfunction "VCC_3V3_116") (pintype "input"))
      (node (ref "U1") (pin "117") (pinfunction "VCC_3V3_117") (pintype "input"))
      (node (ref "U2") (pin "116") (pinfunction "VCC_3V3_116") (pintype "input"))
      (node (ref "U2") (pin "117") (pinfunction "VCC_3V3_117") (pintype "input"))
      (node (ref "U9") (pin "18") (pinfunction "18_18") (pintype "unspecified"))
      (node (ref "U9") (pin "20") (pinfunction "20_20") (pintype "unspecified"))
    )
    (net (code "82") (name "VCC_5V") (class "Default")
      (node (ref "C1") (pin "2") (pinfunction "2_2") (pintype "input"))
      (node (ref "C2") (pin "2") (pinfunction "2_2") (pintype "input"))
      (node (ref "D5") (pin "2") (pinfunction "A_2") (pintype "unspecified"))
      (node (ref "Q1") (pin "1") (pinfunction "G_1") (pintype "unspecified"))
      (node (ref "R1") (pin "2") (pinfunction "2_2") (pintype "input"))
      (node (ref "R68") (pin "2") (pinfunction "2_2") (pintype "input"))
      (node (ref "U8") (pin "1") (pinfunction "1_1") (pintype "unspecified"))
      (node (ref "U8") (pin "11") (pinfunction "11_11") (pintype "unspecified"))
      (node (ref "U8") (pin "3") (pinfunction "3_3") (pintype "unspecified"))
      (node (ref "U8") (pin "5") (pinfunction "5_5") (pintype "unspecified"))
      (node (ref "U8") (pin "7") (pinfunction "7_7") (pintype "unspecified"))
      (node (ref "U8") (pin "9") (pinfunction "9_9") (pintype "unspecified"))
      (node (ref "USB1") (pin "5V_1") (pinfunction "VBUS_5V_1") (pintype "unspecified"))
      (node (ref "USB1") (pin "5V_2") (pinfunction "VBUS_5V_2") (pintype "unspecified"))
      (node (ref "USB2") (pin "5V_1") (pinfunction "VBUS_5V_1") (pintype "unspecified"))
      (node (ref "USB2") (pin "5V_2") (pinfunction "VBUS_5V_2") (pintype "unspecified"))
    )
    (net (code "83") (name "VCC_DDR") (class "Default")
      (node (ref "U1") (pin "71") (pinfunction "VCC_DDR_71") (pintype "input"))
      (node (ref "U1") (pin "72") (pinfunction "VCC_DDR_72") (pintype "input"))
      (node (ref "U1") (pin "73") (pinfunction "VCC_DDR_73") (pintype "input"))
      (node (ref "U1") (pin "74") (pinfunction "VCC_DDR_74") (pintype "input"))
      (node (ref "U1") (pin "75") (pinfunction "VCC_DDR_75") (pintype "input"))
      (node (ref "U1") (pin "76") (pinfunction "VCC_DDR_76") (pintype "input"))
      (node (ref "U2") (pin "71") (pinfunction "VCC_DDR_71") (pintype "input"))
      (node (ref "U2") (pin "72") (pinfunction "VCC_DDR_72") (pintype "input"))
      (node (ref "U2") (pin "73") (pinfunction "VCC_DDR_73") (pintype "input"))
      (node (ref "U2") (pin "74") (pinfunction "VCC_DDR_74") (pintype "input"))
      (node (ref "U2") (pin "75") (pinfunction "VCC_DDR_75") (pintype "input"))
      (node (ref "U2") (pin "76") (pinfunction "VCC_DDR_76") (pintype "input"))
    )
    (net (code "84") (name "VCC_IN") (class "Default")
      (node (ref "D5") (pin "1") (pinfunction "K_1") (pintype "unspecified"))
      (node (ref "Q1") (pin "2") (pinfunction "S_2") (pintype "unspecified"))
      (node (ref "U2") (pin "23") (pinfunction "USB_OTG0_VBUSDET_23") (pintype "input"))
      (node (ref "U2") (pin "24") (pinfunction "USB_OTG0_N_24") (pintype "input"))
      (node (ref "U2") (pin "25") (pinfunction "USB_OTG0_P_25") (pintype "input"))
    )
    (net (code "85") (name "VCC_OUT") (class "Default")
      (node (ref "C3") (pin "2") (pinfunction "2_2") (pintype "input"))
      (node (ref "Q1") (pin "3") (pinfunction "D_3") (pintype "unspecified"))
      (node (ref "U8") (pin "10") (pinfunction "10_10") (pintype "unspecified"))
      (node (ref "U8") (pin "12") (pinfunction "12_12") (pintype "unspecified"))
      (node (ref "U8") (pin "2") (pinfunction "2_2") (pintype "unspecified"))
      (node (ref "U8") (pin "4") (pinfunction "4_4") (pintype "unspecified"))
      (node (ref "U8") (pin "6") (pinfunction "6_6") (pintype "unspecified"))
      (node (ref "U8") (pin "8") (pinfunction "8_8") (pintype "unspecified"))
    )
    (net (code "86") (name "VDDA0V9_IMAGE") (class "Default")
      (node (ref "U1") (pin "2") (pinfunction "VDDA0V9_IMAGE_2") (pintype "input"))
      (node (ref "U2") (pin "2") (pinfunction "VDDA0V9_IMAGE_2") (pintype "input"))
    )
    (net (code "87") (name "VDD_CPU") (class "Default")
      (node (ref "U1") (pin "42") (pinfunction "VDD_CPU_42") (pintype "input"))
      (node (ref "U1") (pin "43") (pinfunction "VDD_CPU_43") (pintype "input"))
      (node (ref "U1") (pin "44") (pinfunction "VDD_CPU_44") (pintype "input"))
      (node (ref "U1") (pin "45") (pinfunction "VDD_CPU_45") (pintype "input"))
      (node (ref "U2") (pin "42") (pinfunction "VDD_CPU_42") (pintype "input"))
      (node (ref "U2") (pin "43") (pinfunction "VDD_CPU_43") (pintype "input"))
      (node (ref "U2") (pin "44") (pinfunction "VDD_CPU_44") (pintype "input"))
      (node (ref "U2") (pin "45") (pinfunction "VDD_CPU_45") (pintype "input"))
    )
    (net (code "88") (name "VDD_GPU") (class "Default")
      (node (ref "U1") (pin "113") (pinfunction "VDD_GPU_113") (pintype "input"))
      (node (ref "U1") (pin "114") (pinfunction "VDD_GPU_114") (pintype "input"))
      (node (ref "U1") (pin "115") (pinfunction "VDD_GPU_115") (pintype "input"))
      (node (ref "U2") (pin "113") (pinfunction "VDD_GPU_113") (pintype "input"))
      (node (ref "U2") (pin "114") (pinfunction "VDD_GPU_114") (pintype "input"))
      (node (ref "U2") (pin "115") (pinfunction "VDD_GPU_115") (pintype "input"))
    )
    (net (code "89") (name "VDD_LOGIC") (class "Default")
      (node (ref "U1") (pin "107") (pinfunction "VDD_LOGIC_107") (pintype "input"))
      (node (ref "U1") (pin "108") (pinfunction "VDD_LOGIC_108") (pintype "input"))
      (node (ref "U1") (pin "109") (pinfunction "VDD_LOGIC_109") (pintype "input"))
      (node (ref "U1") (pin "110") (pinfunction "VDD_LOGIC_110") (pintype "input"))
      (node (ref "U2") (pin "107") (pinfunction "VDD_LOGIC_107") (pintype "input"))
      (node (ref "U2") (pin "108") (pinfunction "VDD_LOGIC_108") (pintype "input"))
      (node (ref "U2") (pin "109") (pinfunction "VDD_LOGIC_109") (pintype "input"))
      (node (ref "U2") (pin "110") (pinfunction "VDD_LOGIC_110") (pintype "input"))
    )
    (net (code "90") (name "VDD_NPU") (class "Default")
      (node (ref "U1") (pin "33") (pinfunction "VDD_NPU_33") (pintype "input"))
      (node (ref "U1") (pin "34") (pinfunction "VDD_NPU_34") (pintype "input"))
      (node (ref "U1") (pin "35") (pinfunction "VDD_NPU_35") (pintype "input"))
      (node (ref "U1") (pin "36") (pinfunction "VDD_NPU_36") (pintype "input"))
      (node (ref "U2") (pin "33") (pinfunction "VDD_NPU_33") (pintype "input"))
      (node (ref "U2") (pin "34") (pinfunction "VDD_NPU_34") (pintype "input"))
      (node (ref "U2") (pin "35") (pinfunction "VDD_NPU_35") (pintype "input"))
      (node (ref "U2") (pin "36") (pinfunction "VDD_NPU_36") (pintype "input"))
    )
    (net (code "91") (name "unconnected-(U1-HDMITX_CEC_M0-Pad1)") (class "Default")
      (node (ref "U1") (pin "1") (pinfunction "HDMITX_CEC_M0_1") (pintype "input+no_connect"))
    )
    (net (code "92") (name "unconnected-(U1-HDMITX_SCL-Pad6)") (class "Default")
      (node (ref "U1") (pin "6") (pinfunction "HDMITX_SCL_6") (pintype "input+no_connect"))
    )
    (net (code "93") (name "unconnected-(U1-HDMITX_SDA-Pad5)") (class "Default")
      (node (ref "U1") (pin "5") (pinfunction "HDMITX_SDA_5") (pintype "input+no_connect"))
    )
    (net (code "94") (name "unconnected-(U1-HDMI_TX_CLK_N-Pad8)") (class "Default")
      (node (ref "U1") (pin "8") (pinfunction "HDMI_TX_CLK_N_8") (pintype "input+no_connect"))
    )
    (net (code "95") (name "unconnected-(U1-HDMI_TX_CLK_P-Pad9)") (class "Default")
      (node (ref "U1") (pin "9") (pinfunction "HDMI_TX_CLK_P_9") (pintype "input+no_connect"))
    )
    (net (code "96") (name "unconnected-(U1-HDMI_TX_D0_N-Pad10)") (class "Default")
      (node (ref "U1") (pin "10") (pinfunction "HDMI_TX_D0_N_10") (pintype "input+no_connect"))
    )
    (net (code "97") (name "unconnected-(U1-HDMI_TX_D0_P-Pad11)") (class "Default")
      (node (ref "U1") (pin "11") (pinfunction "HDMI_TX_D0_P_11") (pintype "input+no_connect"))
    )
    (net (code "98") (name "unconnected-(U1-HDMI_TX_D1_N-Pad12)") (class "Default")
      (node (ref "U1") (pin "12") (pinfunction "HDMI_TX_D1_N_12") (pintype "input+no_connect"))
    )
    (net (code "99") (name "unconnected-(U1-HDMI_TX_D1_P-Pad13)") (class "Default")
      (node (ref "U1") (pin "13") (pinfunction "HDMI_TX_D1_P_13") (pintype "input+no_connect"))
    )
    (net (code "100") (name "unconnected-(U1-HDMI_TX_D2_N-Pad14)") (class "Default")
      (node (ref "U1") (pin "14") (pinfunction "HDMI_TX_D2_N_14") (pintype "input+no_connect"))
    )
    (net (code "101") (name "unconnected-(U1-HDMI_TX_D2_P-Pad15)") (class "Default")
      (node (ref "U1") (pin "15") (pinfunction "HDMI_TX_D2_P_15") (pintype "input+no_connect"))
    )
    (net (code "102") (name "unconnected-(U1-HDMI_TX_HPDIN-Pad4)") (class "Default")
      (node (ref "U1") (pin "4") (pinfunction "HDMI_TX_HPDIN_4") (pintype "input+no_connect"))
    )
    (net (code "103") (name "unconnected-(U1-SDMMC0_CLK-Pad105)") (class "Default")
      (node (ref "U1") (pin "105") (pinfunction "SDMMC0_CLK_105") (pintype "input+no_connect"))
    )
    (net (code "104") (name "unconnected-(U1-SDMMC0_CMD-Pad102)") (class "Default")
      (node (ref "U1") (pin "102") (pinfunction "SDMMC0_CMD_102") (pintype "input+no_connect"))
    )
    (net (code "105") (name "unconnected-(U1-SDMMC0_D0-Pad103)") (class "Default")
      (node (ref "U1") (pin "103") (pinfunction "SDMMC0_D0_103") (pintype "input+no_connect"))
    )
    (net (code "106") (name "unconnected-(U1-SDMMC0_D1-Pad101)") (class "Default")
      (node (ref "U1") (pin "101") (pinfunction "SDMMC0_D1_101") (pintype "input+no_connect"))
    )
    (net (code "107") (name "unconnected-(U1-SDMMC0_D2-Pad104)") (class "Default")
      (node (ref "U1") (pin "104") (pinfunction "SDMMC0_D2_104") (pintype "input+no_connect"))
    )
    (net (code "108") (name "unconnected-(U1-SDMMC0_D3-Pad100)") (class "Default")
      (node (ref "U1") (pin "100") (pinfunction "SDMMC0_D3_100") (pintype "input+no_connect"))
    )
    (net (code "109") (name "unconnected-(U1-SDMMC0_DET_L-Pad20)") (class "Default")
      (node (ref "U1") (pin "20") (pinfunction "SDMMC0_DET_L_20") (pintype "input+no_connect"))
    )
    (net (code "110") (name "unconnected-(U2-MIC1P-Pad96)") (class "Default")
      (node (ref "U2") (pin "96") (pinfunction "MIC1P_96") (pintype "input+no_connect"))
    )
    (net (code "111") (name "unconnected-(U2-NC-Pad1)") (class "Default")
      (node (ref "U2") (pin "1") (pinfunction "NC_1") (pintype "input"))
    )
    (net (code "112") (name "unconnected-(U2-NC-Pad100)") (class "Default")
      (node (ref "U2") (pin "100") (pinfunction "NC_100") (pintype "input"))
    )
    (net (code "113") (name "unconnected-(U2-NC-Pad101)") (class "Default")
      (node (ref "U2") (pin "101") (pinfunction "NC_101") (pintype "input"))
    )
    (net (code "114") (name "unconnected-(U2-NC-Pad102)") (class "Default")
      (node (ref "U2") (pin "102") (pinfunction "NC_102") (pintype "input"))
    )
    (net (code "115") (name "unconnected-(U2-NC-Pad103)") (class "Default")
      (node (ref "U2") (pin "103") (pinfunction "NC_103") (pintype "input"))
    )
    (net (code "116") (name "unconnected-(U2-NC-Pad104)") (class "Default")
      (node (ref "U2") (pin "104") (pinfunction "NC_104") (pintype "input"))
    )
    (net (code "117") (name "unconnected-(U2-NC-Pad105)") (class "Default")
      (node (ref "U2") (pin "105") (pinfunction "NC_105") (pintype "input"))
    )
    (net (code "118") (name "unconnected-(U2-SDMMC0_DET_L-Pad20)") (class "Default")
      (node (ref "U2") (pin "20") (pinfunction "SDMMC0_DET_L_20") (pintype "input+no_connect"))
    )
    (net (code "119") (name "unconnected-(U2-SPK_OUTN-Pad98)") (class "Default")
      (node (ref "U2") (pin "98") (pinfunction "SPK_OUTN_98") (pintype "input+no_connect"))
    )
    (net (code "120") (name "unconnected-(U2-SPK_OUTP-Pad97)") (class "Default")
      (node (ref "U2") (pin "97") (pinfunction "SPK_OUTP_97") (pintype "input+no_connect"))
    )
    (net (code "121") (name "unconnected-(U8-Pad13)") (class "Default")
      (node (ref "U8") (pin "13") (pinfunction "13_13") (pintype "unspecified+no_connect"))
    )
    (net (code "122") (name "unconnected-(U8-Pad14)") (class "Default")
      (node (ref "U8") (pin "14") (pinfunction "14_14") (pintype "unspecified+no_connect"))
    )
    (net (code "123") (name "unconnected-(U8-Pad15)") (class "Default")
      (node (ref "U8") (pin "15") (pinfunction "15_15") (pintype "unspecified+no_connect"))
    )
    (net (code "124") (name "unconnected-(U8-Pad16)") (class "Default")
      (node (ref "U8") (pin "16") (pinfunction "16_16") (pintype "unspecified+no_connect"))
    )
    (net (code "125") (name "unconnected-(U9-Pad7)") (class "Default")
      (node (ref "U9") (pin "7") (pinfunction "7_7") (pintype "unspecified+no_connect"))
    )
    (net (code "126") (name "unconnected-(U9-Pad8)") (class "Default")
      (node (ref "U9") (pin "8") (pinfunction "8_8") (pintype "unspecified+no_connect"))
    )
    (net (code "127") (name "unconnected-(U9-Pad11)") (class "Default")
      (node (ref "U9") (pin "11") (pinfunction "11_11") (pintype "unspecified+no_connect"))
    )
    (net (code "128") (name "unconnected-(U9-Pad12)") (class "Default")
      (node (ref "U9") (pin "12") (pinfunction "12_12") (pintype "unspecified+no_connect"))
    )
    (net (code "129") (name "unconnected-(U9-Pad15)") (class "Default")
      (node (ref "U9") (pin "15") (pinfunction "15_15") (pintype "unspecified+no_connect"))
    )
    (net (code "130") (name "unconnected-(U9-Pad16)") (class "Default")
      (node (ref "U9") (pin "16") (pinfunction "16_16") (pintype "unspecified+no_connect"))
    )
    (net (code "131") (name "unconnected-(U9-Pad21)") (class "Default")
      (node (ref "U9") (pin "21") (pinfunction "21_21") (pintype "unspecified+no_connect"))
    )
    (net (code "132") (name "unconnected-(U9-Pad22)") (class "Default")
      (node (ref "U9") (pin "22") (pinfunction "22_22") (pintype "unspecified+no_connect"))
    )
    (net (code "133") (name "unconnected-(U9-Pad23)") (class "Default")
      (node (ref "U9") (pin "23") (pinfunction "23_23") (pintype "unspecified+no_connect"))
    )
    (net (code "134") (name "unconnected-(U9-Pad24)") (class "Default")
      (node (ref "U9") (pin "24") (pinfunction "24_24") (pintype "unspecified+no_connect"))
    )
    (net (code "135") (name "unconnected-(USB1-SBU1-PadA8)") (class "Default")
      (node (ref "USB1") (pin "A8") (pinfunction "SBU1_A8") (pintype "unspecified+no_connect"))
    )
    (net (code "136") (name "unconnected-(USB1-SBU2-PadB8)") (class "Default")
      (node (ref "USB1") (pin "B8") (pinfunction "SBU2_B8") (pintype "unspecified+no_connect"))
    )
    (net (code "137") (name "unconnected-(USB2-CC1-PadA5)") (class "Default")
      (node (ref "USB2") (pin "A5") (pinfunction "CC1_A5") (pintype "unspecified+no_connect"))
    )
    (net (code "138") (name "unconnected-(USB2-CC2-PadB5)") (class "Default")
      (node (ref "USB2") (pin "B5") (pinfunction "CC2_B5") (pintype "unspecified+no_connect"))
    )
    (net (code "139") (name "unconnected-(USB2-SBU1-PadA8)") (class "Default")
      (node (ref "USB2") (pin "A8") (pinfunction "SBU1_A8") (pintype "unspecified+no_connect"))
    )
    (net (code "140") (name "unconnected-(USB2-SBU2-PadB8)") (class "Default")
      (node (ref "USB2") (pin "B8") (pinfunction "SBU2_B8") (pintype "unspecified+no_connect"))
    )
  )
)
